# Voltage_Regulation.net
KiCad netlist of a schematic drawn in Altium Designer
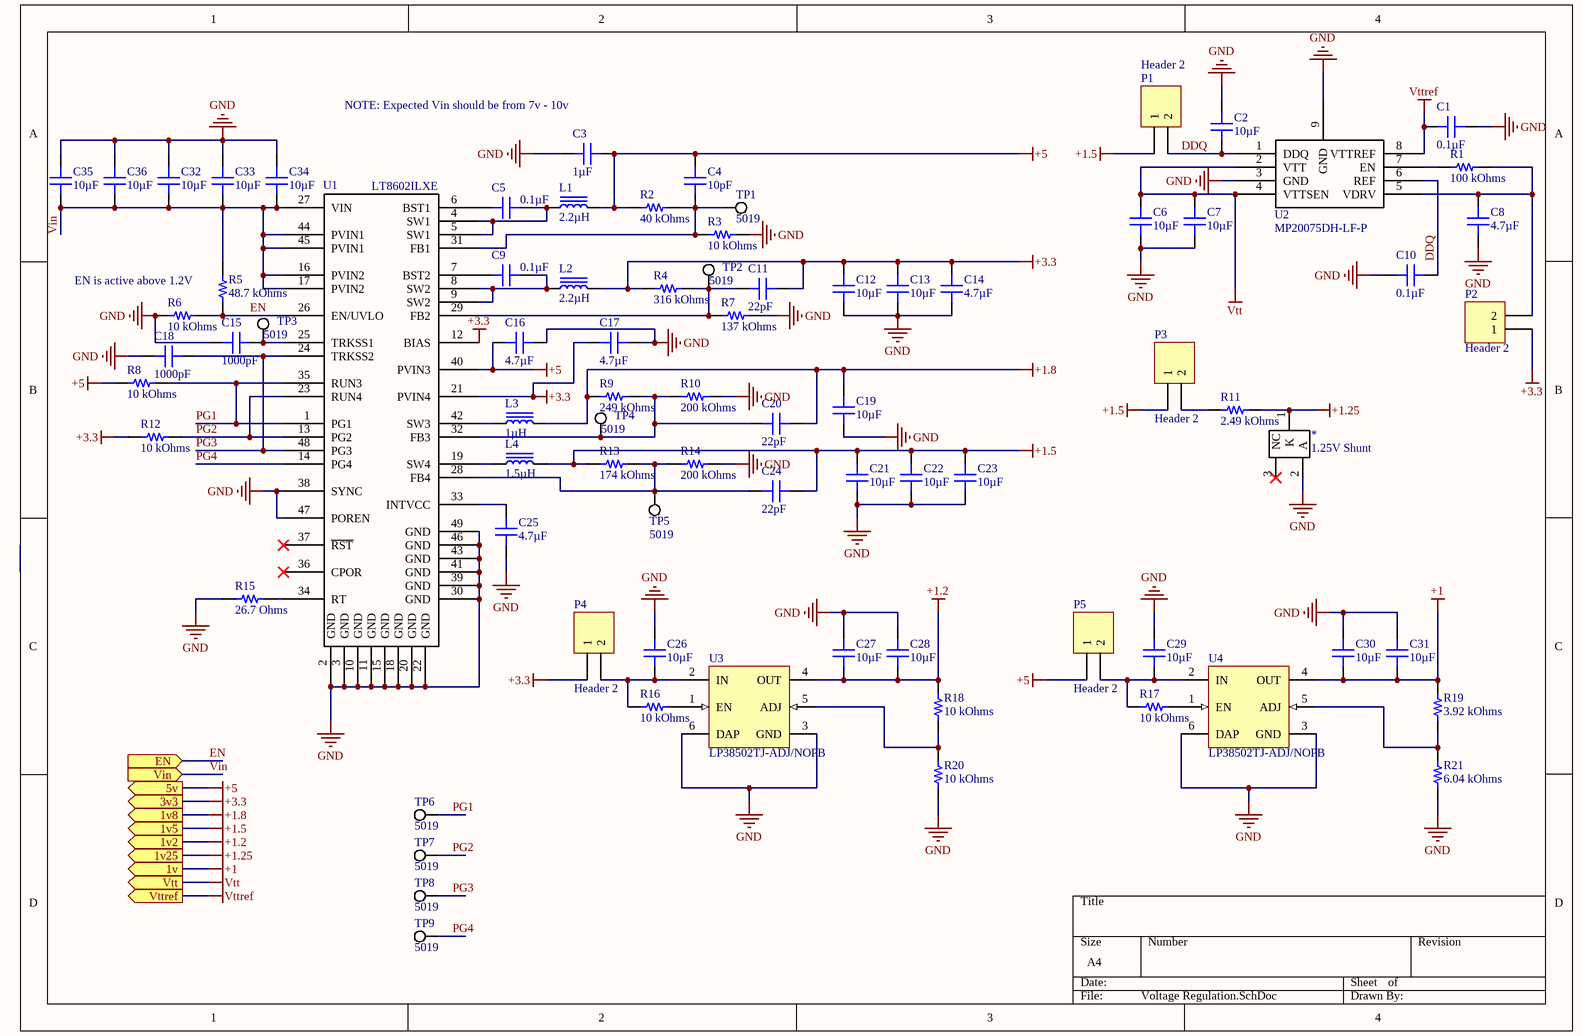
[diagram p0: Voltage Regulation.SchDoc]

(export (version "E")
  (design (tool "Eeschema 10.0.6"))
  (components
    (comp (ref "*")
      (value "1.25V Shunt")
      (footprint "TS4061AILT-1.25")
      (libsource (lib "2020-09-26_17-27-19") (part "1.25V Shunt"))
    )
    (comp (ref "C1")
      (value "0.1µF")
      (footprint "CAP 0805_2012")
      (description "CAP CER 0.1UF 50V X7R 0805")
      (fields (field (name "PART NUMBER") "08055C104KAT4A") (field (name "MANUFACTURER") "AVX Corporation"))
      (libsource (lib "Celestial Altium Library - altium_library") (part "Capacitor"))
    )
    (comp (ref "C2")
      (value "10µF")
      (footprint "CAP 0805_2012")
      (description "CAP CER 10UF 6.3V X7R 0805")
      (fields
        (field (name "PART NUMBER") "CL21B106KQQNFNE")
        (field (name "MANUFACTURER") "Samsung Electro-Mechanics")
      )
      (libsource (lib "Celestial Altium Library - altium_library") (part "Capacitor"))
    )
    (comp (ref "C3")
      (value "1µF")
      (footprint "CAP 0805_2012")
      (description "CAP CER 1UF 25V X7R 0805")
      (fields (field (name "PART NUMBER") "885012207078") (field (name "MANUFACTURER") "Würth Elektronik"))
      (libsource (lib "Celestial Altium Library - altium_library") (part "Capacitor"))
    )
    (comp (ref "C4")
      (value "10pF")
      (footprint "CAP 0805_2012")
      (description "CAP CER 10PF 50V C0G/NP0 0805")
      (fields (field (name "PART NUMBER") "C0805C100K5GACTU") (field (name "MANUFACTURER") "KEMET"))
      (libsource (lib "Celestial Altium Library - altium_library") (part "Capacitor"))
    )
    (comp (ref "C5")
      (value "0.1µF")
      (footprint "CAP 0805_2012")
      (description "CAP CER 0.1UF 50V X7R 0805")
      (fields (field (name "PART NUMBER") "C0805C104M5RACTU") (field (name "MANUFACTURER") "KEMET"))
      (libsource (lib "Celestial Altium Library - altium_library") (part "Capacitor"))
    )
    (comp (ref "C6")
      (value "10µF")
      (footprint "CAP 0805_2012")
      (description "CAP CER 10UF 6.3V X7R 0805")
      (fields
        (field (name "PART NUMBER") "CL21B106KQQNFNE")
        (field (name "MANUFACTURER") "Samsung Electro-Mechanics")
      )
      (libsource (lib "Celestial Altium Library - altium_library") (part "Capacitor"))
    )
    (comp (ref "C7")
      (value "10µF")
      (footprint "CAP 0805_2012")
      (description "CAP CER 10UF 6.3V X7R 0805")
      (fields
        (field (name "PART NUMBER") "CL21B106KQQNFNE")
        (field (name "MANUFACTURER") "Samsung Electro-Mechanics")
      )
      (libsource (lib "Celestial Altium Library - altium_library") (part "Capacitor"))
    )
    (comp (ref "C8")
      (value "4.7µF")
      (footprint "CAP 0805_2012")
      (description "CAP CER 4.7UF 16V X7R 0805")
      (fields
        (field (name "PART NUMBER") "GRM21BR71C475KE51L")
        (field (name "MANUFACTURER") "Murata Electronics")
      )
      (libsource (lib "Celestial Altium Library - altium_library") (part "Capacitor"))
    )
    (comp (ref "C9")
      (value "0.1µF")
      (footprint "CAP 0805_2012")
      (description "CAP CER 0.1UF 50V X7R 0805")
      (fields (field (name "PART NUMBER") "C0805C104M5RACTU") (field (name "MANUFACTURER") "KEMET"))
      (libsource (lib "Celestial Altium Library - altium_library") (part "Capacitor"))
    )
    (comp (ref "C10")
      (value "0.1µF")
      (footprint "CAP 0805_2012")
      (description "CAP CER 0.1UF 50V X7R 0805")
      (fields (field (name "PART NUMBER") "08055C104KAT4A") (field (name "MANUFACTURER") "AVX Corporation"))
      (libsource (lib "Celestial Altium Library - altium_library") (part "Capacitor"))
    )
    (comp (ref "C11")
      (value "22pF")
      (footprint "CAP 0805_2012")
      (description "CAP CER SMD 0805 22PF 5% 50V X7R")
      (fields (field (name "PART NUMBER") "C0805C220J5RAC7800") (field (name "MANUFACTURER") "KEMET"))
      (libsource (lib "Celestial Altium Library - altium_library") (part "Capacitor"))
    )
    (comp (ref "C12")
      (value "10µF")
      (footprint "CAP 0805_2012")
      (description "CAP CER 10UF 6.3V X7R 0805")
      (fields
        (field (name "PART NUMBER") "CL21B106KQQNFNE")
        (field (name "MANUFACTURER") "Samsung Electro-Mechanics")
      )
      (libsource (lib "Celestial Altium Library - altium_library") (part "Capacitor"))
    )
    (comp (ref "C13")
      (value "10µF")
      (footprint "CAP 0805_2012")
      (description "CAP CER 10UF 6.3V X7R 0805")
      (fields
        (field (name "PART NUMBER") "CL21B106KQQNFNE")
        (field (name "MANUFACTURER") "Samsung Electro-Mechanics")
      )
      (libsource (lib "Celestial Altium Library - altium_library") (part "Capacitor"))
    )
    (comp (ref "C14")
      (value "4.7µF")
      (footprint "CAP 0805_2012")
      (description "CAP CER 4.7UF 16V X7R 0805")
      (fields
        (field (name "PART NUMBER") "GRM21BR71C475KE51L")
        (field (name "MANUFACTURER") "Murata Electronics")
      )
      (libsource (lib "Celestial Altium Library - altium_library") (part "Capacitor"))
    )
    (comp (ref "C15")
      (value "1000pF")
      (footprint "CAP 0805_2012")
      (description "CAP CER 1000PF 16V X7R 0805")
      (fields (field (name "PART NUMBER") "885012207033") (field (name "MANUFACTURER") "Würth Elektronik"))
      (libsource (lib "Celestial Altium Library - altium_library") (part "Capacitor"))
    )
    (comp (ref "C16")
      (value "4.7µF")
      (footprint "CAP 0805_2012")
      (description "CAP CER 4.7UF 16V X7R 0805")
      (fields
        (field (name "PART NUMBER") "GRM21BR71C475KE51L")
        (field (name "MANUFACTURER") "Murata Electronics")
      )
      (libsource (lib "Celestial Altium Library - altium_library") (part "Capacitor"))
    )
    (comp (ref "C17")
      (value "4.7µF")
      (footprint "CAP 0805_2012")
      (description "CAP CER 4.7UF 16V X7R 0805")
      (fields
        (field (name "PART NUMBER") "GRM21BR71C475KE51L")
        (field (name "MANUFACTURER") "Murata Electronics")
      )
      (libsource (lib "Celestial Altium Library - altium_library") (part "Capacitor"))
    )
    (comp (ref "C18")
      (value "1000pF")
      (footprint "CAP 0805_2012")
      (description "CAP CER 1000PF 16V X7R 0805")
      (fields (field (name "PART NUMBER") "885012207033") (field (name "MANUFACTURER") "Würth Elektronik"))
      (libsource (lib "Celestial Altium Library - altium_library") (part "Capacitor"))
    )
    (comp (ref "C19")
      (value "10µF")
      (footprint "CAP 0805_2012")
      (description "CAP CER 10UF 6.3V X7R 0805")
      (fields
        (field (name "PART NUMBER") "CL21B106KQQNFNE")
        (field (name "MANUFACTURER") "Samsung Electro-Mechanics")
      )
      (libsource (lib "Celestial Altium Library - altium_library") (part "Capacitor"))
    )
    (comp (ref "C20")
      (value "22pF")
      (footprint "CAP 0805_2012")
      (description "CAP CER SMD 0805 22PF 5% 50V X7R")
      (fields (field (name "PART NUMBER") "C0805C220J5RAC7800") (field (name "MANUFACTURER") "KEMET"))
      (libsource (lib "Celestial Altium Library - altium_library") (part "Capacitor"))
    )
    (comp (ref "C21")
      (value "10µF")
      (footprint "CAP 0805_2012")
      (description "CAP CER 10UF 6.3V X7R 0805")
      (fields
        (field (name "PART NUMBER") "CL21B106KQQNFNE")
        (field (name "MANUFACTURER") "Samsung Electro-Mechanics")
      )
      (libsource (lib "Celestial Altium Library - altium_library") (part "Capacitor"))
    )
    (comp (ref "C22")
      (value "10µF")
      (footprint "CAP 0805_2012")
      (description "CAP CER 10UF 6.3V X7R 0805")
      (fields
        (field (name "PART NUMBER") "CL21B106KQQNFNE")
        (field (name "MANUFACTURER") "Samsung Electro-Mechanics")
      )
      (libsource (lib "Celestial Altium Library - altium_library") (part "Capacitor"))
    )
    (comp (ref "C23")
      (value "10µF")
      (footprint "CAP 0805_2012")
      (description "CAP CER 10UF 6.3V X7R 0805")
      (fields
        (field (name "PART NUMBER") "CL21B106KQQNFNE")
        (field (name "MANUFACTURER") "Samsung Electro-Mechanics")
      )
      (libsource (lib "Celestial Altium Library - altium_library") (part "Capacitor"))
    )
    (comp (ref "C24")
      (value "22pF")
      (footprint "CAP 0805_2012")
      (description "CAP CER SMD 0805 22PF 5% 50V X7R")
      (fields (field (name "PART NUMBER") "C0805C220J5RAC7800") (field (name "MANUFACTURER") "KEMET"))
      (libsource (lib "Celestial Altium Library - altium_library") (part "Capacitor"))
    )
    (comp (ref "C25")
      (value "4.7µF")
      (footprint "CAP 0805_2012")
      (description "CAP CER 4.7UF 16V X7R 0805")
      (fields
        (field (name "PART NUMBER") "GRM21BR71C475KE51L")
        (field (name "MANUFACTURER") "Murata Electronics")
      )
      (libsource (lib "Celestial Altium Library - altium_library") (part "Capacitor"))
    )
    (comp (ref "C26")
      (value "10µF")
      (footprint "CAP 0805_2012")
      (description "CAP CER 10UF 6.3V X7R 0805")
      (fields
        (field (name "PART NUMBER") "CL21B106KQQNFNE")
        (field (name "MANUFACTURER") "Samsung Electro-Mechanics")
      )
      (libsource (lib "Celestial Altium Library - altium_library") (part "Capacitor"))
    )
    (comp (ref "C27")
      (value "10µF")
      (footprint "CAP 0805_2012")
      (description "CAP CER 10UF 6.3V X7R 0805")
      (fields
        (field (name "PART NUMBER") "CL21B106KQQNFNE")
        (field (name "MANUFACTURER") "Samsung Electro-Mechanics")
      )
      (libsource (lib "Celestial Altium Library - altium_library") (part "Capacitor"))
    )
    (comp (ref "C28")
      (value "10µF")
      (footprint "CAP 0805_2012")
      (description "CAP CER 10UF 6.3V X7R 0805")
      (fields
        (field (name "PART NUMBER") "CL21B106KQQNFNE")
        (field (name "MANUFACTURER") "Samsung Electro-Mechanics")
      )
      (libsource (lib "Celestial Altium Library - altium_library") (part "Capacitor"))
    )
    (comp (ref "C29")
      (value "10µF")
      (footprint "CAP 0805_2012")
      (description "CAP CER 10UF 6.3V X7R 0805")
      (fields
        (field (name "PART NUMBER") "CL21B106KQQNFNE")
        (field (name "MANUFACTURER") "Samsung Electro-Mechanics")
      )
      (libsource (lib "Celestial Altium Library - altium_library") (part "Capacitor"))
    )
    (comp (ref "C30")
      (value "10µF")
      (footprint "CAP 0805_2012")
      (description "CAP CER 10UF 6.3V X7R 0805")
      (fields
        (field (name "PART NUMBER") "CL21B106KQQNFNE")
        (field (name "MANUFACTURER") "Samsung Electro-Mechanics")
      )
      (libsource (lib "Celestial Altium Library - altium_library") (part "Capacitor"))
    )
    (comp (ref "C31")
      (value "10µF")
      (footprint "CAP 0805_2012")
      (description "CAP CER 10UF 6.3V X7R 0805")
      (fields
        (field (name "PART NUMBER") "CL21B106KQQNFNE")
        (field (name "MANUFACTURER") "Samsung Electro-Mechanics")
      )
      (libsource (lib "Celestial Altium Library - altium_library") (part "Capacitor"))
    )
    (comp (ref "C32")
      (value "10µF")
      (footprint "CAP 0805_2012")
      (description "CAP CER 10UF 6.3V X7R 0805")
      (fields
        (field (name "PART NUMBER") "CL21B106KQQNFNE")
        (field (name "MANUFACTURER") "Samsung Electro-Mechanics")
      )
      (libsource (lib "Celestial Altium Library - altium_library") (part "Capacitor"))
    )
    (comp (ref "C33")
      (value "10µF")
      (footprint "CAP 0805_2012")
      (description "CAP CER 10UF 6.3V X7R 0805")
      (fields
        (field (name "PART NUMBER") "CL21B106KQQNFNE")
        (field (name "MANUFACTURER") "Samsung Electro-Mechanics")
      )
      (libsource (lib "Celestial Altium Library - altium_library") (part "Capacitor"))
    )
    (comp (ref "C34")
      (value "10µF")
      (footprint "CAP 0805_2012")
      (description "CAP CER 10UF 6.3V X7R 0805")
      (fields
        (field (name "PART NUMBER") "CL21B106KQQNFNE")
        (field (name "MANUFACTURER") "Samsung Electro-Mechanics")
      )
      (libsource (lib "Celestial Altium Library - altium_library") (part "Capacitor"))
    )
    (comp (ref "C35")
      (value "10µF")
      (footprint "CAP 0805_2012")
      (description "CAP CER 10UF 6.3V X7R 0805")
      (fields
        (field (name "PART NUMBER") "CL21B106KQQNFNE")
        (field (name "MANUFACTURER") "Samsung Electro-Mechanics")
      )
      (libsource (lib "Celestial Altium Library - altium_library") (part "Capacitor"))
    )
    (comp (ref "C36")
      (value "10µF")
      (footprint "CAP 0805_2012")
      (description "CAP CER 10UF 6.3V X7R 0805")
      (fields
        (field (name "PART NUMBER") "CL21B106KQQNFNE")
        (field (name "MANUFACTURER") "Samsung Electro-Mechanics")
      )
      (libsource (lib "Celestial Altium Library - altium_library") (part "Capacitor"))
    )
    (comp (ref "L1")
      (value "2.2µH")
      (footprint "WURTH WE-LQS 6045")
      (description "FIXED IND 2.2UH 4.6A 14 MOHM SMD")
      (fields (field (name "PART NUMBER") "74404064022") (field (name "MANUFACTURER") "Würth Elektronik"))
      (libsource (lib "Celestial Altium Library - altium_library") (part "Inductor"))
    )
    (comp (ref "L2")
      (value "2.2µH")
      (footprint "WURTH WE-LQS 6045")
      (description "FIXED IND 2.2UH 4.6A 14 MOHM SMD")
      (fields (field (name "PART NUMBER") "74404064022") (field (name "MANUFACTURER") "Würth Elektronik"))
      (libsource (lib "Celestial Altium Library - altium_library") (part "Inductor"))
    )
    (comp (ref "L3")
      (value "1µH")
      (footprint "IND 0806_2016")
      (description "FIXED IND 1UH 2.7A 72 MOHM SMD")
      (fields
        (field (name "PART NUMBER") "VLS201612HBX-1R0M-1")
        (field (name "MANUFACTURER") "TDK Corporation")
      )
      (libsource (lib "Celestial Altium Library - altium_library") (part "Inductor"))
    )
    (comp (ref "L4")
      (value "1.5µH")
      (footprint "TDK VLS252012HBX-1")
      (description "FIXED IND 1.5UH 2.75A 82 MOHM")
      (fields
        (field (name "PART NUMBER") "VLS252012HBX-1R5M-1")
        (field (name "MANUFACTURER") "TDK Corporation")
      )
      (libsource (lib "Celestial Altium Library - altium_library") (part "Inductor"))
    )
    (comp (ref "P1")
      (value "Header 2")
      (footprint "HDR1X2")
      (description "Header, 2-Pin")
      (fields (field (name "PUBLISHER") "Altium Limited"))
      (libsource (lib "Miscellaneous Connectors") (part "Header 2"))
    )
    (comp (ref "P2")
      (value "Header 2")
      (footprint "HDR1X2")
      (description "Header, 2-Pin")
      (fields (field (name "PUBLISHER") "Altium Limited"))
      (libsource (lib "") (part "Header 2_1"))
    )
    (comp (ref "P3")
      (value "Header 2")
      (footprint "HDR1X2")
      (description "Header, 2-Pin")
      (fields (field (name "PUBLISHER") "Altium Limited"))
      (libsource (lib "Miscellaneous Connectors") (part "Header 2"))
    )
    (comp (ref "P4")
      (value "Header 2")
      (footprint "HDR1X2")
      (description "Header, 2-Pin")
      (fields (field (name "PUBLISHER") "Altium Limited"))
      (libsource (lib "Miscellaneous Connectors") (part "Header 2"))
    )
    (comp (ref "P5")
      (value "Header 2")
      (footprint "HDR1X2")
      (description "Header, 2-Pin")
      (fields (field (name "PUBLISHER") "Altium Limited"))
      (libsource (lib "Miscellaneous Connectors") (part "Header 2"))
    )
    (comp (ref "R1")
      (value "100 kOhms")
      (footprint "RES 0805_2012")
      (description "RES SMD 100K OHM 1% 1/8W 0805")
      (fields (field (name "PART NUMBER") "CR0805-FX-1003ELF") (field (name "MANUFACTURER") "Bourns Inc."))
      (libsource (lib "Celestial Altium Library - altium_library") (part "Resistor"))
    )
    (comp (ref "R2")
      (value "40 kOhms")
      (footprint "RES 0805_2012")
      (description "RES SMD 40K OHM 1% 1/8W 0805")
      (fields (field (name "PART NUMBER") "CRCW080540K0FKEA") (field (name "MANUFACTURER") "Vishay Dale"))
      (libsource (lib "Celestial Altium Library - altium_library") (part "Resistor"))
    )
    (comp (ref "R3")
      (value "10 kOhms")
      (footprint "RES 0805_2012")
      (description "RES 10K OHM 1% 1/8W 0805")
      (fields
        (field (name "PART NUMBER") "RMCF0805FT10K0")
        (field (name "MANUFACTURER") "Stackpole Electronics Inc")
      )
      (libsource (lib "Celestial Altium Library - altium_library") (part "Resistor"))
    )
    (comp (ref "R4")
      (value "316 kOhms")
      (footprint "RES 0805_2012")
      (description "RES SMD 316K OHM 1% 1/8W 0805")
      (fields
        (field (name "PART NUMBER") "ERJ-6ENF3163V")
        (field (name "MANUFACTURER") "Panasonic Electronic Components")
      )
      (libsource (lib "Celestial Altium Library - altium_library") (part "Resistor"))
    )
    (comp (ref "R5")
      (value "48.7 kOhms")
      (footprint "RES 0805_2012")
      (description "RES SMD 48.7K OHM 1% 1/8W 0805")
      (fields (field (name "PART NUMBER") "RC0805FR-0748K7L") (field (name "MANUFACTURER") "Yageo"))
      (libsource (lib "Celestial Altium Library - altium_library") (part "Resistor"))
    )
    (comp (ref "R6")
      (value "10 kOhms")
      (footprint "RES 0805_2012")
      (description "RES 10K OHM 1% 1/8W 0805")
      (fields
        (field (name "PART NUMBER") "RMCF0805FT10K0")
        (field (name "MANUFACTURER") "Stackpole Electronics Inc")
      )
      (libsource (lib "Celestial Altium Library - altium_library") (part "Resistor"))
    )
    (comp (ref "R7")
      (value "137 kOhms")
      (footprint "RES 0805_2012")
      (description "RES SMD 137K OHM 1% 1/8W 0805")
      (fields (field (name "PART NUMBER") "RC0805FR-07137KL") (field (name "MANUFACTURER") "Yageo"))
      (libsource (lib "Celestial Altium Library - altium_library") (part "Resistor"))
    )
    (comp (ref "R8")
      (value "10 kOhms")
      (footprint "RES 0805_2012")
      (description "RES 10K OHM 1% 1/8W 0805")
      (fields
        (field (name "PART NUMBER") "RMCF0805FT10K0")
        (field (name "MANUFACTURER") "Stackpole Electronics Inc")
      )
      (libsource (lib "Celestial Altium Library - altium_library") (part "Resistor"))
    )
    (comp (ref "R9")
      (value "249 kOhms")
      (footprint "RES 0805_2012")
      (description "RES SMD 249K OHM 1% 1/8W 0805")
      (fields
        (field (name "PART NUMBER") "ERJ-6ENF2493V")
        (field (name "MANUFACTURER") "Panasonic Electronic Components")
      )
      (libsource (lib "Celestial Altium Library - altium_library") (part "Resistor"))
    )
    (comp (ref "R10")
      (value "200 kOhms")
      (footprint "RES 0805_2012")
      (description "RES SMD 200K OHM 1% 1/8W 0805")
      (fields (field (name "PART NUMBER") "AC0805FR-07200KL") (field (name "MANUFACTURER") "Yageo"))
      (libsource (lib "Celestial Altium Library - altium_library") (part "Resistor"))
    )
    (comp (ref "R11")
      (value "2.49 kOhms")
      (footprint "RES 0805_2012")
      (description "RES 2.49K OHM 1% 1/8W 0805")
      (fields
        (field (name "PART NUMBER") "RMCF0805FT2K49")
        (field (name "MANUFACTURER") "Stackpole Electronics Inc")
      )
      (libsource (lib "Celestial Altium Library - altium_library") (part "Resistor"))
    )
    (comp (ref "R12")
      (value "10 kOhms")
      (footprint "RES 0805_2012")
      (description "RES 10K OHM 1% 1/8W 0805")
      (fields
        (field (name "PART NUMBER") "RMCF0805FT10K0")
        (field (name "MANUFACTURER") "Stackpole Electronics Inc")
      )
      (libsource (lib "Celestial Altium Library - altium_library") (part "Resistor"))
    )
    (comp (ref "R13")
      (value "174 kOhms")
      (footprint "RES 0805_2012")
      (description "RES SMD 174K OHM 1% 1/8W 0805")
      (fields
        (field (name "PART NUMBER") "ERJ-6ENF1743V")
        (field (name "MANUFACTURER") "Panasonic Electronic Components")
      )
      (libsource (lib "Celestial Altium Library - altium_library") (part "Resistor"))
    )
    (comp (ref "R14")
      (value "200 kOhms")
      (footprint "RES 0805_2012")
      (description "RES SMD 200K OHM 1% 1/8W 0805")
      (fields (field (name "PART NUMBER") "AC0805FR-07200KL") (field (name "MANUFACTURER") "Yageo"))
      (libsource (lib "Celestial Altium Library - altium_library") (part "Resistor"))
    )
    (comp (ref "R15")
      (value "26.7 Ohms")
      (footprint "RES 0805_2012")
      (description "RES SMD 26.7 OHM 1% 1/8W 0805")
      (fields
        (field (name "PART NUMBER") "ERJ-6ENF26R7V")
        (field (name "MANUFACTURER") "Panasonic Electronic Components")
      )
      (libsource (lib "Celestial Altium Library - altium_library") (part "Resistor"))
    )
    (comp (ref "R16")
      (value "10 kOhms")
      (footprint "RES 0805_2012")
      (description "RES 10K OHM 1% 1/8W 0805")
      (fields
        (field (name "PART NUMBER") "RMCF0805FT10K0")
        (field (name "MANUFACTURER") "Stackpole Electronics Inc")
      )
      (libsource (lib "Celestial Altium Library - altium_library") (part "Resistor"))
    )
    (comp (ref "R17")
      (value "10 kOhms")
      (footprint "RES 0805_2012")
      (description "RES 10K OHM 1% 1/8W 0805")
      (fields
        (field (name "PART NUMBER") "RMCF0805FT10K0")
        (field (name "MANUFACTURER") "Stackpole Electronics Inc")
      )
      (libsource (lib "Celestial Altium Library - altium_library") (part "Resistor"))
    )
    (comp (ref "R18")
      (value "10 kOhms")
      (footprint "RES 0805_2012")
      (description "RES 10K OHM 1% 1/8W 0805")
      (fields
        (field (name "PART NUMBER") "RMCF0805FT10K0")
        (field (name "MANUFACTURER") "Stackpole Electronics Inc")
      )
      (libsource (lib "Celestial Altium Library - altium_library") (part "Resistor"))
    )
    (comp (ref "R19")
      (value "3.92 kOhms")
      (footprint "RES 0805_2012")
      (description "RES SMD 3.92K OHM 1% 1/8W 0805")
      (fields
        (field (name "PART NUMBER") "ERJ-6ENF3921V")
        (field (name "MANUFACTURER") "Panasonic Electronic Components")
      )
      (libsource (lib "Celestial Altium Library - altium_library") (part "Resistor"))
    )
    (comp (ref "R20")
      (value "10 kOhms")
      (footprint "RES 0805_2012")
      (description "RES 10K OHM 1% 1/8W 0805")
      (fields
        (field (name "PART NUMBER") "RMCF0805FT10K0")
        (field (name "MANUFACTURER") "Stackpole Electronics Inc")
      )
      (libsource (lib "Celestial Altium Library - altium_library") (part "Resistor"))
    )
    (comp (ref "R21")
      (value "6.04 kOhms")
      (footprint "RES 0805_2012")
      (description "RES SMD 6.04K OHM 1% 1/8W 0805")
      (fields
        (field (name "PART NUMBER") "ERJ-6ENF6041V")
        (field (name "MANUFACTURER") "Panasonic Electronic Components")
      )
      (libsource (lib "Celestial Altium Library - altium_library") (part "Resistor"))
    )
    (comp (ref "TP1")
      (value "5019")
      (footprint "KSTN-5019_V")
      (description "Test Point, 1 Position SMD, RoHS, Tape and Reel")
      (libsource (lib "Altium Content Vault") (part "TESTPOINT_WHITE"))
    )
    (comp (ref "TP2")
      (value "5019")
      (footprint "KSTN-5019_V")
      (description "Test Point, 1 Position SMD, RoHS, Tape and Reel")
      (libsource (lib "Altium Content Vault") (part "TESTPOINT_WHITE"))
    )
    (comp (ref "TP3")
      (value "5019")
      (footprint "KSTN-5019_V")
      (description "Test Point, 1 Position SMD, RoHS, Tape and Reel")
      (libsource (lib "Altium Content Vault") (part "TESTPOINT_WHITE"))
    )
    (comp (ref "TP4")
      (value "5019")
      (footprint "KSTN-5019_V")
      (description "Test Point, 1 Position SMD, RoHS, Tape and Reel")
      (libsource (lib "Altium Content Vault") (part "TESTPOINT_WHITE"))
    )
    (comp (ref "TP5")
      (value "5019")
      (footprint "KSTN-5019_V")
      (description "Test Point, 1 Position SMD, RoHS, Tape and Reel")
      (libsource (lib "Altium Content Vault") (part "TESTPOINT_WHITE"))
    )
    (comp (ref "TP6")
      (value "5019")
      (footprint "KSTN-5019_V")
      (description "Test Point, 1 Position SMD, RoHS, Tape and Reel")
      (libsource (lib "Altium Content Vault") (part "TESTPOINT_WHITE"))
    )
    (comp (ref "TP7")
      (value "5019")
      (footprint "KSTN-5019_V")
      (description "Test Point, 1 Position SMD, RoHS, Tape and Reel")
      (libsource (lib "Altium Content Vault") (part "TESTPOINT_WHITE"))
    )
    (comp (ref "TP8")
      (value "5019")
      (footprint "KSTN-5019_V")
      (description "Test Point, 1 Position SMD, RoHS, Tape and Reel")
      (libsource (lib "Altium Content Vault") (part "TESTPOINT_WHITE"))
    )
    (comp (ref "TP9")
      (value "5019")
      (footprint "KSTN-5019_V")
      (description "Test Point, 1 Position SMD, RoHS, Tape and Reel")
      (libsource (lib "Altium Content Vault") (part "TESTPOINT_WHITE"))
    )
    (comp (ref "U1")
      (value "LT8602ILXE")
      (footprint "Quad48")
      (libsource (lib "2020-09-26_17-27-19") (part "LT8602"))
    )
    (comp (ref "U2")
      (value "MP20075DH-LF-P")
      (footprint "MP20075")
      (libsource (lib "2020-09-26_17-27-19") (part "MP20075DH-LF-P"))
    )
    (comp (ref "U3")
      (value "LP38502TJ-ADJ/NOPB")
      (footprint "NDQ0005A_L")
      (description "1.5A FlexCap Low Dropout Linear Regulator for 2.7V to 5.5V Inputs, 5-pin TO-263 Thin, Pb-Free")
      (fields (field (name "MANUFACTURER") "Texas Instruments"))
      (libsource (lib "Altium Content Vault") (part "PM-REG-LP38502-DAP6"))
    )
    (comp (ref "U4")
      (value "LP38502TJ-ADJ/NOPB")
      (footprint "NDQ0005A_L")
      (description "1.5A FlexCap Low Dropout Linear Regulator for 2.7V to 5.5V Inputs, 5-pin TO-263 Thin, Pb-Free")
      (fields (field (name "MANUFACTURER") "Texas Instruments"))
      (libsource (lib "Altium Content Vault") (part "PM-REG-LP38502-DAP6"))
    )
  )
  (nets
    (net (code "1") (name "+1") (class "Default")
      (node (ref "C30") (pin "1") (pinfunction "1_1") (pintype "passive"))
      (node (ref "C31") (pin "1") (pinfunction "1_1") (pintype "passive"))
      (node (ref "R19") (pin "2") (pinfunction "2_2") (pintype "passive"))
      (node (ref "U4") (pin "4") (pinfunction "OUT_4") (pintype "power_in"))
    )
    (net (code "2") (name "+1.2") (class "Default")
      (node (ref "C27") (pin "1") (pinfunction "1_1") (pintype "passive"))
      (node (ref "C28") (pin "1") (pinfunction "1_1") (pintype "passive"))
      (node (ref "R18") (pin "2") (pinfunction "2_2") (pintype "passive"))
      (node (ref "U3") (pin "4") (pinfunction "OUT_4") (pintype "power_in"))
    )
    (net (code "3") (name "+1.5") (class "Default")
      (node (ref "C21") (pin "2") (pinfunction "2_2") (pintype "passive"))
      (node (ref "C22") (pin "2") (pinfunction "2_2") (pintype "passive"))
      (node (ref "C23") (pin "2") (pinfunction "2_2") (pintype "passive"))
      (node (ref "C24") (pin "2") (pinfunction "2_2") (pintype "passive"))
      (node (ref "L4") (pin "2") (pinfunction "2_2") (pintype "passive"))
      (node (ref "P1") (pin "1") (pinfunction "1_1") (pintype "passive"))
      (node (ref "P3") (pin "1") (pinfunction "1_1") (pintype "passive"))
      (node (ref "R13") (pin "1") (pinfunction "1_1") (pintype "passive"))
    )
    (net (code "4") (name "+1.8") (class "Default")
      (node (ref "C19") (pin "2") (pinfunction "2_2") (pintype "passive"))
      (node (ref "C20") (pin "2") (pinfunction "2_2") (pintype "passive"))
      (node (ref "L3") (pin "2") (pinfunction "2_2") (pintype "passive"))
      (node (ref "R9") (pin "1") (pinfunction "1_1") (pintype "passive"))
    )
    (net (code "5") (name "+1.25") (class "Default")
      (node (ref "*") (pin "1") (pinfunction "K_1") (pintype "passive"))
      (node (ref "R11") (pin "2") (pinfunction "2_2") (pintype "passive"))
    )
    (net (code "6") (name "+3.3") (class "Default")
      (node (ref "C11") (pin "2") (pinfunction "2_2") (pintype "passive"))
      (node (ref "C12") (pin "2") (pinfunction "2_2") (pintype "passive"))
      (node (ref "C13") (pin "2") (pinfunction "2_2") (pintype "passive"))
      (node (ref "C14") (pin "2") (pinfunction "2_2") (pintype "passive"))
      (node (ref "C17") (pin "2") (pinfunction "2_2") (pintype "passive"))
      (node (ref "L2") (pin "2") (pinfunction "2_2") (pintype "passive"))
      (node (ref "P2") (pin "1") (pinfunction "1_1") (pintype "passive"))
      (node (ref "P4") (pin "1") (pinfunction "1_1") (pintype "passive"))
      (node (ref "R12") (pin "1") (pinfunction "1_1") (pintype "passive"))
      (node (ref "R4") (pin "1") (pinfunction "1_1") (pintype "passive"))
      (node (ref "U1") (pin "12") (pinfunction "BIAS_12") (pintype "passive"))
      (node (ref "U1") (pin "21") (pinfunction "PVIN4_21") (pintype "passive"))
    )
    (net (code "7") (name "+5") (class "Default")
      (node (ref "C16") (pin "2") (pinfunction "2_2") (pintype "passive"))
      (node (ref "C3") (pin "2") (pinfunction "2_2") (pintype "passive"))
      (node (ref "C4") (pin "2") (pinfunction "2_2") (pintype "passive"))
      (node (ref "L1") (pin "2") (pinfunction "2_2") (pintype "passive"))
      (node (ref "P5") (pin "1") (pinfunction "1_1") (pintype "passive"))
      (node (ref "R2") (pin "1") (pinfunction "1_1") (pintype "passive"))
      (node (ref "R8") (pin "1") (pinfunction "1_1") (pintype "passive"))
      (node (ref "U1") (pin "40") (pinfunction "PVIN3_40") (pintype "passive"))
    )
    (net (code "8") (name "/DDQ") (class "Default")
      (node (ref "C10") (pin "2") (pinfunction "2_2") (pintype "passive"))
      (node (ref "C2") (pin "1") (pinfunction "1_1") (pintype "passive"))
      (node (ref "P1") (pin "2") (pinfunction "2_2") (pintype "passive"))
      (node (ref "U2") (pin "1") (pinfunction "DDQ_1") (pintype "passive"))
      (node (ref "U2") (pin "6") (pinfunction "REF_6") (pintype "passive"))
    )
    (net (code "9") (name "/EN") (class "Default")
      (node (ref "R5") (pin "1") (pinfunction "1_1") (pintype "passive"))
      (node (ref "R6") (pin "2") (pinfunction "2_2") (pintype "passive"))
      (node (ref "U1") (pin "26") (pinfunction "EN/UVLO_26") (pintype "passive"))
    )
    (net (code "10") (name "/PG1") (class "Default")
      (node (ref "R8") (pin "2") (pinfunction "2_2") (pintype "passive"))
      (node (ref "TP6") (pin "1") (pinfunction "1_1") (pintype "passive"))
      (node (ref "U1") (pin "1") (pinfunction "PG1_1") (pintype "passive"))
      (node (ref "U1") (pin "35") (pinfunction "RUN3_35") (pintype "passive"))
    )
    (net (code "11") (name "/PG2") (class "Default")
      (node (ref "R12") (pin "2") (pinfunction "2_2") (pintype "passive"))
      (node (ref "TP7") (pin "1") (pinfunction "1_1") (pintype "passive"))
      (node (ref "U1") (pin "13") (pinfunction "PG2_13") (pintype "passive"))
      (node (ref "U1") (pin "23") (pinfunction "RUN4_23") (pintype "passive"))
    )
    (net (code "12") (name "/PG3") (class "Default")
      (node (ref "C18") (pin "2") (pinfunction "2_2") (pintype "passive"))
      (node (ref "TP8") (pin "1") (pinfunction "1_1") (pintype "passive"))
      (node (ref "U1") (pin "24") (pinfunction "TRKSS2_24") (pintype "passive"))
      (node (ref "U1") (pin "48") (pinfunction "PG3_48") (pintype "passive"))
    )
    (net (code "13") (name "/PG4") (class "Default")
      (node (ref "TP9") (pin "1") (pinfunction "1_1") (pintype "passive"))
      (node (ref "U1") (pin "14") (pinfunction "PG4_14") (pintype "passive"))
    )
    (net (code "14") (name "/Vin") (class "Default")
      (node (ref "C32") (pin "1") (pinfunction "1_1") (pintype "passive"))
      (node (ref "C33") (pin "1") (pinfunction "1_1") (pintype "passive"))
      (node (ref "C34") (pin "1") (pinfunction "1_1") (pintype "passive"))
      (node (ref "C35") (pin "1") (pinfunction "1_1") (pintype "passive"))
      (node (ref "C36") (pin "1") (pinfunction "1_1") (pintype "passive"))
      (node (ref "R5") (pin "2") (pinfunction "2_2") (pintype "passive"))
      (node (ref "U1") (pin "16") (pinfunction "PVIN2_16") (pintype "passive"))
      (node (ref "U1") (pin "17") (pinfunction "PVIN2_17") (pintype "passive"))
      (node (ref "U1") (pin "27") (pinfunction "VIN_27") (pintype "passive"))
      (node (ref "U1") (pin "44") (pinfunction "PVIN1_44") (pintype "passive"))
      (node (ref "U1") (pin "45") (pinfunction "PVIN1_45") (pintype "passive"))
    )
    (net (code "15") (name "GND") (class "Default")
      (node (ref "*") (pin "2") (pinfunction "A_2") (pintype "passive"))
      (node (ref "C1") (pin "2") (pinfunction "2_2") (pintype "passive"))
      (node (ref "C10") (pin "1") (pinfunction "1_1") (pintype "passive"))
      (node (ref "C12") (pin "1") (pinfunction "1_1") (pintype "passive"))
      (node (ref "C13") (pin "1") (pinfunction "1_1") (pintype "passive"))
      (node (ref "C14") (pin "1") (pinfunction "1_1") (pintype "passive"))
      (node (ref "C15") (pin "1") (pinfunction "1_1") (pintype "passive"))
      (node (ref "C16") (pin "1") (pinfunction "1_1") (pintype "passive"))
      (node (ref "C17") (pin "1") (pinfunction "1_1") (pintype "passive"))
      (node (ref "C18") (pin "1") (pinfunction "1_1") (pintype "passive"))
      (node (ref "C19") (pin "1") (pinfunction "1_1") (pintype "passive"))
      (node (ref "C2") (pin "2") (pinfunction "2_2") (pintype "passive"))
      (node (ref "C21") (pin "1") (pinfunction "1_1") (pintype "passive"))
      (node (ref "C22") (pin "1") (pinfunction "1_1") (pintype "passive"))
      (node (ref "C23") (pin "1") (pinfunction "1_1") (pintype "passive"))
      (node (ref "C25") (pin "1") (pinfunction "1_1") (pintype "passive"))
      (node (ref "C26") (pin "2") (pinfunction "2_2") (pintype "passive"))
      (node (ref "C27") (pin "2") (pinfunction "2_2") (pintype "passive"))
      (node (ref "C28") (pin "2") (pinfunction "2_2") (pintype "passive"))
      (node (ref "C29") (pin "2") (pinfunction "2_2") (pintype "passive"))
      (node (ref "C3") (pin "1") (pinfunction "1_1") (pintype "passive"))
      (node (ref "C30") (pin "2") (pinfunction "2_2") (pintype "passive"))
      (node (ref "C31") (pin "2") (pinfunction "2_2") (pintype "passive"))
      (node (ref "C32") (pin "2") (pinfunction "2_2") (pintype "passive"))
      (node (ref "C33") (pin "2") (pinfunction "2_2") (pintype "passive"))
      (node (ref "C34") (pin "2") (pinfunction "2_2") (pintype "passive"))
      (node (ref "C35") (pin "2") (pinfunction "2_2") (pintype "passive"))
      (node (ref "C36") (pin "2") (pinfunction "2_2") (pintype "passive"))
      (node (ref "C6") (pin "1") (pinfunction "1_1") (pintype "passive"))
      (node (ref "C7") (pin "1") (pinfunction "1_1") (pintype "passive"))
      (node (ref "C8") (pin "1") (pinfunction "1_1") (pintype "passive"))
      (node (ref "R10") (pin "2") (pinfunction "2_2") (pintype "passive"))
      (node (ref "R14") (pin "2") (pinfunction "2_2") (pintype "passive"))
      (node (ref "R15") (pin "1") (pinfunction "1_1") (pintype "passive"))
      (node (ref "R20") (pin "1") (pinfunction "1_1") (pintype "passive"))
      (node (ref "R21") (pin "1") (pinfunction "1_1") (pintype "passive"))
      (node (ref "R3") (pin "2") (pinfunction "2_2") (pintype "passive"))
      (node (ref "R6") (pin "1") (pinfunction "1_1") (pintype "passive"))
      (node (ref "R7") (pin "2") (pinfunction "2_2") (pintype "passive"))
      (node (ref "U1") (pin "10") (pinfunction "GND_10") (pintype "passive"))
      (node (ref "U1") (pin "11") (pinfunction "GND_11") (pintype "passive"))
      (node (ref "U1") (pin "15") (pinfunction "GND_15") (pintype "passive"))
      (node (ref "U1") (pin "18") (pinfunction "GND_18") (pintype "passive"))
      (node (ref "U1") (pin "2") (pinfunction "GND_2") (pintype "passive"))
      (node (ref "U1") (pin "20") (pinfunction "GND_20") (pintype "passive"))
      (node (ref "U1") (pin "22") (pinfunction "GND_22") (pintype "passive"))
      (node (ref "U1") (pin "3") (pinfunction "GND_3") (pintype "passive"))
      (node (ref "U1") (pin "30") (pinfunction "GND_30") (pintype "passive"))
      (node (ref "U1") (pin "38") (pinfunction "SYNC_38") (pintype "passive"))
      (node (ref "U1") (pin "39") (pinfunction "GND_39") (pintype "passive"))
      (node (ref "U1") (pin "41") (pinfunction "GND_41") (pintype "passive"))
      (node (ref "U1") (pin "43") (pinfunction "GND_43") (pintype "passive"))
      (node (ref "U1") (pin "46") (pinfunction "GND_46") (pintype "passive"))
      (node (ref "U1") (pin "47") (pinfunction "POREN_47") (pintype "passive"))
      (node (ref "U1") (pin "49") (pinfunction "GND_49") (pintype "passive"))
      (node (ref "U2") (pin "3") (pinfunction "GND_3") (pintype "passive"))
      (node (ref "U2") (pin "9") (pinfunction "GND_9") (pintype "passive"))
      (node (ref "U3") (pin "3") (pinfunction "GND_3") (pintype "power_in"))
      (node (ref "U3") (pin "6") (pinfunction "DAP_6") (pintype "power_in"))
      (node (ref "U4") (pin "3") (pinfunction "GND_3") (pintype "power_in"))
      (node (ref "U4") (pin "6") (pinfunction "DAP_6") (pintype "power_in"))
    )
    (net (code "16") (name "Net-(C5-Pad2)") (class "Default")
      (node (ref "C5") (pin "2") (pinfunction "2_2") (pintype "passive"))
      (node (ref "L1") (pin "1") (pinfunction "1_1") (pintype "passive"))
      (node (ref "U1") (pin "4") (pinfunction "SW1_4") (pintype "passive"))
      (node (ref "U1") (pin "5") (pinfunction "SW1_5") (pintype "passive"))
    )
    (net (code "17") (name "Net-(C9-Pad2)") (class "Default")
      (node (ref "C9") (pin "2") (pinfunction "2_2") (pintype "passive"))
      (node (ref "L2") (pin "1") (pinfunction "1_1") (pintype "passive"))
      (node (ref "U1") (pin "8") (pinfunction "SW2_8") (pintype "passive"))
      (node (ref "U1") (pin "9") (pinfunction "SW2_9") (pintype "passive"))
    )
    (net (code "18") (name "Net-(P3-Pad2)") (class "Default")
      (node (ref "P3") (pin "2") (pinfunction "2_2") (pintype "passive"))
      (node (ref "R11") (pin "1") (pinfunction "1_1") (pintype "passive"))
    )
    (net (code "19") (name "Net-(U1-BST1)") (class "Default")
      (node (ref "C5") (pin "1") (pinfunction "1_1") (pintype "passive"))
      (node (ref "U1") (pin "6") (pinfunction "BST1_6") (pintype "passive"))
    )
    (net (code "20") (name "Net-(U1-BST2)") (class "Default")
      (node (ref "C9") (pin "1") (pinfunction "1_1") (pintype "passive"))
      (node (ref "U1") (pin "7") (pinfunction "BST2_7") (pintype "passive"))
    )
    (net (code "21") (name "Net-(U1-FB1)") (class "Default")
      (node (ref "C4") (pin "1") (pinfunction "1_1") (pintype "passive"))
      (node (ref "R2") (pin "2") (pinfunction "2_2") (pintype "passive"))
      (node (ref "R3") (pin "1") (pinfunction "1_1") (pintype "passive"))
      (node (ref "TP1") (pin "1") (pinfunction "1_1") (pintype "passive"))
      (node (ref "U1") (pin "31") (pinfunction "FB1_31") (pintype "passive"))
    )
    (net (code "22") (name "Net-(U1-FB2)") (class "Default")
      (node (ref "C11") (pin "1") (pinfunction "1_1") (pintype "passive"))
      (node (ref "R4") (pin "2") (pinfunction "2_2") (pintype "passive"))
      (node (ref "R7") (pin "1") (pinfunction "1_1") (pintype "passive"))
      (node (ref "TP2") (pin "1") (pinfunction "1_1") (pintype "passive"))
      (node (ref "U1") (pin "29") (pinfunction "FB2_29") (pintype "passive"))
    )
    (net (code "23") (name "Net-(U1-FB3)") (class "Default")
      (node (ref "C20") (pin "1") (pinfunction "1_1") (pintype "passive"))
      (node (ref "R10") (pin "1") (pinfunction "1_1") (pintype "passive"))
      (node (ref "R9") (pin "2") (pinfunction "2_2") (pintype "passive"))
      (node (ref "TP4") (pin "1") (pinfunction "1_1") (pintype "passive"))
      (node (ref "U1") (pin "32") (pinfunction "FB3_32") (pintype "passive"))
    )
    (net (code "24") (name "Net-(U1-FB4)") (class "Default")
      (node (ref "C24") (pin "1") (pinfunction "1_1") (pintype "passive"))
      (node (ref "R13") (pin "2") (pinfunction "2_2") (pintype "passive"))
      (node (ref "R14") (pin "1") (pinfunction "1_1") (pintype "passive"))
      (node (ref "TP5") (pin "1") (pinfunction "1_1") (pintype "passive"))
      (node (ref "U1") (pin "28") (pinfunction "FB4_28") (pintype "passive"))
    )
    (net (code "25") (name "Net-(U1-INTVCC)") (class "Default")
      (node (ref "C25") (pin "2") (pinfunction "2_2") (pintype "passive"))
      (node (ref "U1") (pin "33") (pinfunction "INTVCC_33") (pintype "passive"))
    )
    (net (code "26") (name "Net-(U1-RT)") (class "Default")
      (node (ref "R15") (pin "2") (pinfunction "2_2") (pintype "passive"))
      (node (ref "U1") (pin "34") (pinfunction "RT_34") (pintype "passive"))
    )
    (net (code "27") (name "Net-(U1-SW3)") (class "Default")
      (node (ref "L3") (pin "1") (pinfunction "1_1") (pintype "passive"))
      (node (ref "U1") (pin "42") (pinfunction "SW3_42") (pintype "passive"))
    )
    (net (code "28") (name "Net-(U1-SW4)") (class "Default")
      (node (ref "L4") (pin "1") (pinfunction "1_1") (pintype "passive"))
      (node (ref "U1") (pin "19") (pinfunction "SW4_19") (pintype "passive"))
    )
    (net (code "29") (name "Net-(U1-TRKSS1)") (class "Default")
      (node (ref "C15") (pin "2") (pinfunction "2_2") (pintype "passive"))
      (node (ref "TP3") (pin "1") (pinfunction "1_1") (pintype "passive"))
      (node (ref "U1") (pin "25") (pinfunction "TRKSS1_25") (pintype "passive"))
    )
    (net (code "30") (name "Net-(U2-EN)") (class "Default")
      (node (ref "R1") (pin "2") (pinfunction "2_2") (pintype "passive"))
      (node (ref "U2") (pin "7") (pinfunction "EN_7") (pintype "passive"))
    )
    (net (code "31") (name "Net-(U2-VDRV)") (class "Default")
      (node (ref "C8") (pin "2") (pinfunction "2_2") (pintype "passive"))
      (node (ref "P2") (pin "2") (pinfunction "2_2") (pintype "passive"))
      (node (ref "R1") (pin "1") (pinfunction "1_1") (pintype "passive"))
      (node (ref "U2") (pin "5") (pinfunction "VDRV_5") (pintype "passive"))
    )
    (net (code "32") (name "Net-(U3-ADJ)") (class "Default")
      (node (ref "R18") (pin "1") (pinfunction "1_1") (pintype "passive"))
      (node (ref "R20") (pin "2") (pinfunction "2_2") (pintype "passive"))
      (node (ref "U3") (pin "5") (pinfunction "ADJ_5") (pintype "input"))
    )
    (net (code "33") (name "Net-(U3-EN)") (class "Default")
      (node (ref "R16") (pin "2") (pinfunction "2_2") (pintype "passive"))
      (node (ref "U3") (pin "1") (pinfunction "EN_1") (pintype "input"))
    )
    (net (code "34") (name "Net-(U3-IN)") (class "Default")
      (node (ref "C26") (pin "1") (pinfunction "1_1") (pintype "passive"))
      (node (ref "P4") (pin "2") (pinfunction "2_2") (pintype "passive"))
      (node (ref "R16") (pin "1") (pinfunction "1_1") (pintype "passive"))
      (node (ref "U3") (pin "2") (pinfunction "IN_2") (pintype "power_in"))
    )
    (net (code "35") (name "Net-(U4-ADJ)") (class "Default")
      (node (ref "R19") (pin "1") (pinfunction "1_1") (pintype "passive"))
      (node (ref "R21") (pin "2") (pinfunction "2_2") (pintype "passive"))
      (node (ref "U4") (pin "5") (pinfunction "ADJ_5") (pintype "input"))
    )
    (net (code "36") (name "Net-(U4-EN)") (class "Default")
      (node (ref "R17") (pin "2") (pinfunction "2_2") (pintype "passive"))
      (node (ref "U4") (pin "1") (pinfunction "EN_1") (pintype "input"))
    )
    (net (code "37") (name "Net-(U4-IN)") (class "Default")
      (node (ref "C29") (pin "1") (pinfunction "1_1") (pintype "passive"))
      (node (ref "P5") (pin "2") (pinfunction "2_2") (pintype "passive"))
      (node (ref "R17") (pin "1") (pinfunction "1_1") (pintype "passive"))
      (node (ref "U4") (pin "2") (pinfunction "IN_2") (pintype "power_in"))
    )
    (net (code "38") (name "Vtt") (class "Default")
      (node (ref "C6") (pin "2") (pinfunction "2_2") (pintype "passive"))
      (node (ref "C7") (pin "2") (pinfunction "2_2") (pintype "passive"))
      (node (ref "U2") (pin "2") (pinfunction "VTT_2") (pintype "passive"))
      (node (ref "U2") (pin "4") (pinfunction "VTTSEN_4") (pintype "passive"))
    )
    (net (code "39") (name "Vttref") (class "Default")
      (node (ref "C1") (pin "1") (pinfunction "1_1") (pintype "passive"))
      (node (ref "U2") (pin "8") (pinfunction "VTTREF_8") (pintype "passive"))
    )
    (net (code "40") (name "unconnected-(*-NC-Pad3)") (class "Default")
      (node (ref "*") (pin "3") (pinfunction "NC_3") (pintype "passive+no_connect"))
    )
    (net (code "41") (name "unconnected-(U1-CPOR-Pad36)") (class "Default")
      (node (ref "U1") (pin "36") (pinfunction "CPOR_36") (pintype "passive+no_connect"))
    )
    (net (code "42") (name "unconnected-(U1-~{RST}-Pad37)") (class "Default")
      (node (ref "U1") (pin "37") (pinfunction "~{RST}_37") (pintype "passive+no_connect"))
    )
  )
)
